# PCB-MIDI-OUT.net
KiCad netlist of a schematic drawn in EAGLE
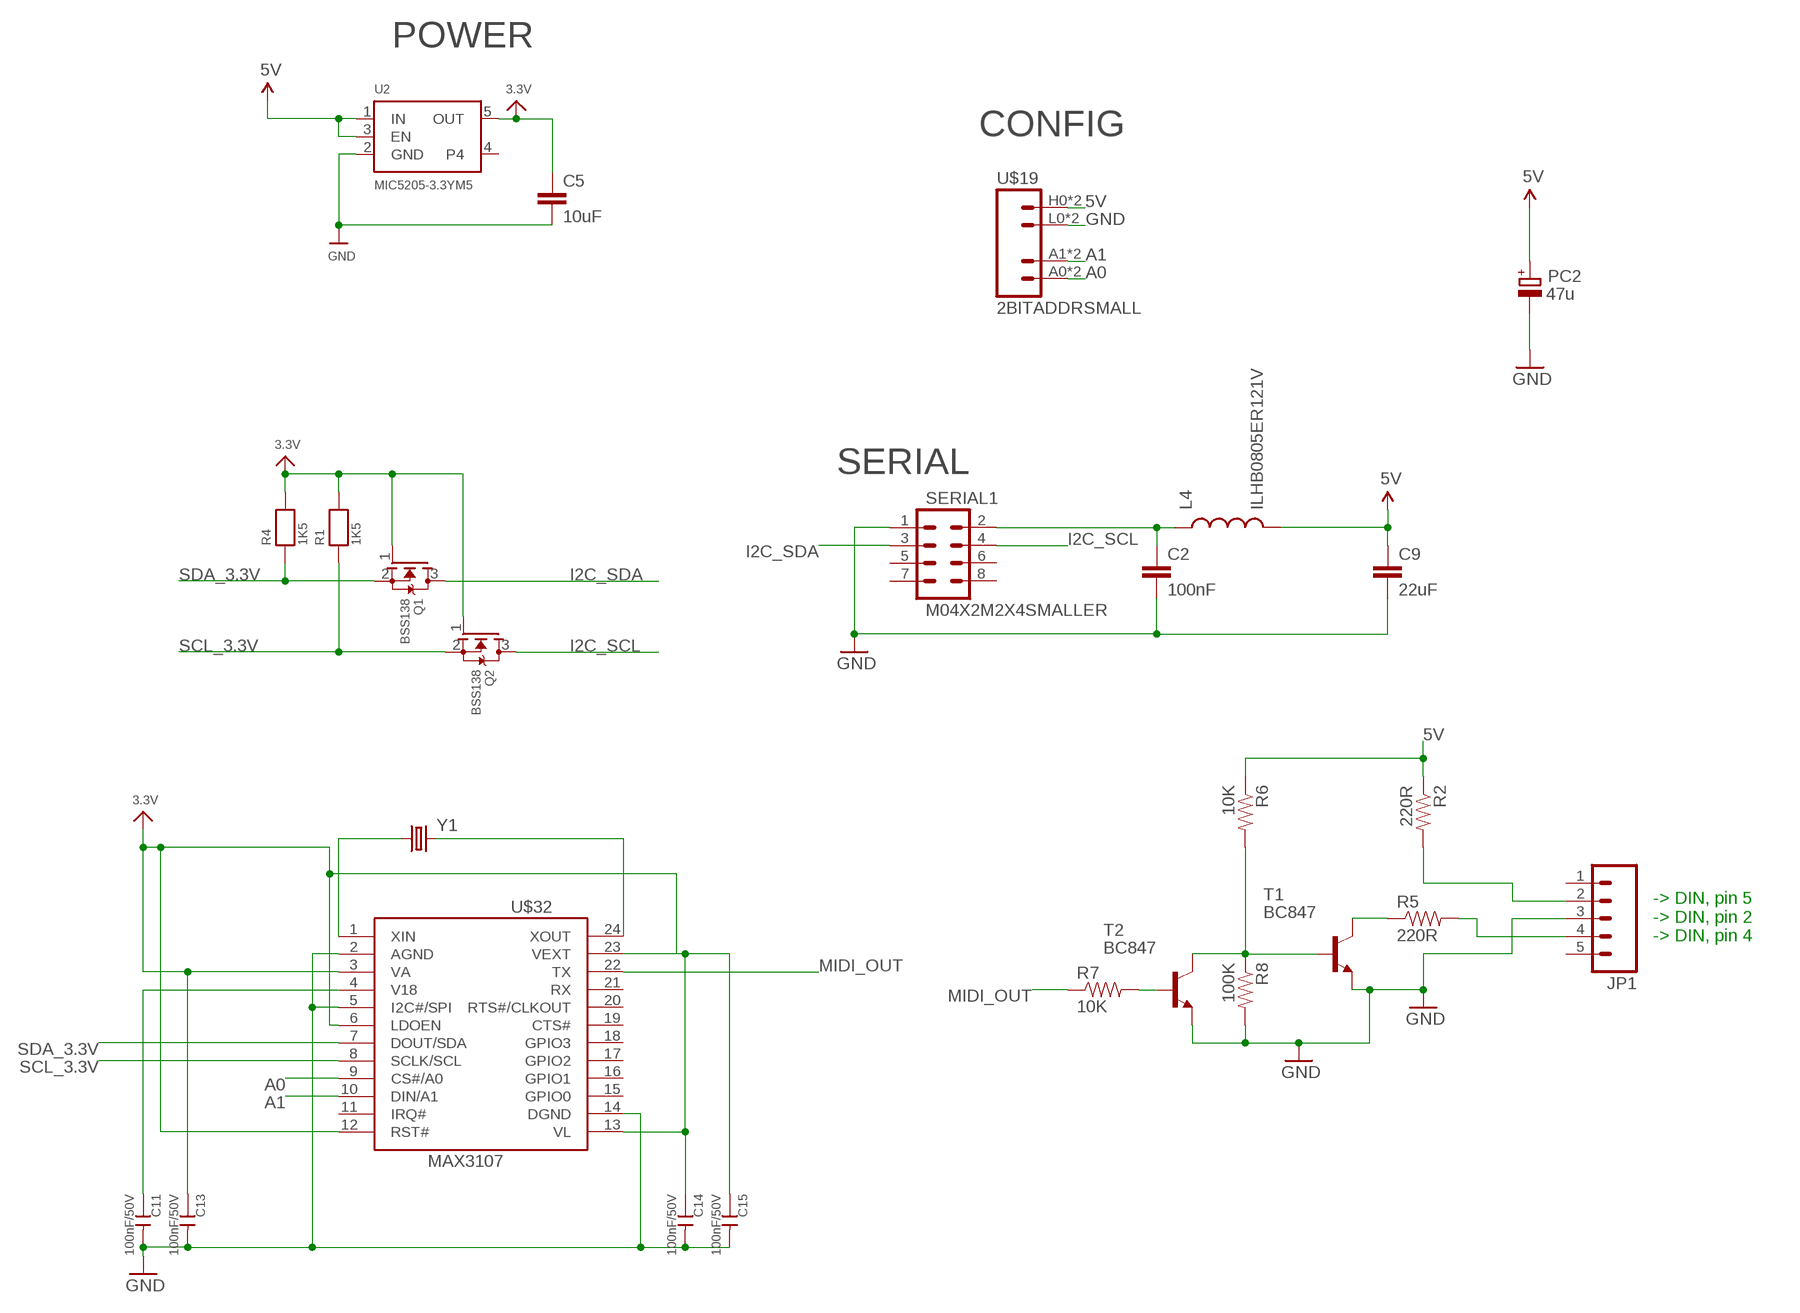
[diagram p0: schematic, sheet 1]

(export (version "E")
  (design (tool "Eeschema 10.0.6"))
  (components
    (comp (ref "C2")
      (value "100nF")
      (footprint "eagle-import:0603-CAP")
      (libsource (lib "eagle-import") (part "CAP0603-CAP"))
    )
    (comp (ref "C5")
      (value "10uF")
      (footprint "eagle-import:0805")
      (libsource (lib "eagle-import") (part "CAP0805"))
    )
    (comp (ref "C9")
      (value "22uF")
      (footprint "eagle-import:0805")
      (libsource (lib "eagle-import") (part "CAP0805"))
    )
    (comp (ref "C11")
      (value "100nF/50V")
      (footprint "eagle-import:C0603")
      (libsource (lib "eagle-import") (part "CAP-0603"))
    )
    (comp (ref "C13")
      (value "100nF/50V")
      (footprint "eagle-import:C0603")
      (libsource (lib "eagle-import") (part "CAP-0603"))
    )
    (comp (ref "C14")
      (value "100nF/50V")
      (footprint "eagle-import:C0603")
      (libsource (lib "eagle-import") (part "CAP-0603"))
    )
    (comp (ref "C15")
      (value "100nF/50V")
      (footprint "eagle-import:C0603")
      (libsource (lib "eagle-import") (part "CAP-0603"))
    )
    (comp (ref "JP1")
      (value "M05LOCK")
      (footprint "eagle-import:1X05_LOCK")
      (libsource (lib "eagle-import") (part "M05LOCK"))
    )
    (comp (ref "L4")
      (value "ILHB0805ER121V")
      (footprint "eagle-import:0805")
      (libsource (lib "eagle-import") (part "INDUCTOR0805"))
    )
    (comp (ref "PC2")
      (value "47u")
      (footprint "eagle-import:PANASONIC_D")
      (libsource (lib "eagle-import") (part "CPOL-EUD"))
    )
    (comp (ref "Q1")
      (value "BSS138")
      (footprint "eagle-import:SOT23-R")
      (libsource (lib "eagle-import") (part "MOSFET-NREFLOW"))
    )
    (comp (ref "Q2")
      (value "BSS138")
      (footprint "eagle-import:SOT23-R")
      (libsource (lib "eagle-import") (part "MOSFET-NREFLOW"))
    )
    (comp (ref "R1")
      (value "1K5")
      (footprint "eagle-import:0603")
      (libsource (lib "eagle-import") (part "RESISTOR0603"))
    )
    (comp (ref "R2")
      (value "220R")
      (footprint "eagle-import:0603-RES")
      (libsource (lib "eagle-import") (part "RESISTOR0603-RES"))
    )
    (comp (ref "R4")
      (value "1K5")
      (footprint "eagle-import:0603")
      (libsource (lib "eagle-import") (part "RESISTOR0603"))
    )
    (comp (ref "R5")
      (value "220R")
      (footprint "eagle-import:0603-RES")
      (libsource (lib "eagle-import") (part "RESISTOR0603-RES"))
    )
    (comp (ref "R6")
      (value "10K")
      (footprint "eagle-import:0603-RES")
      (libsource (lib "eagle-import") (part "RESISTOR0603-RES"))
    )
    (comp (ref "R7")
      (value "10K")
      (footprint "eagle-import:0603-RES")
      (libsource (lib "eagle-import") (part "RESISTOR0603-RES"))
    )
    (comp (ref "R8")
      (value "100K")
      (footprint "eagle-import:0603-RES")
      (libsource (lib "eagle-import") (part "RESISTOR0603-RES"))
    )
    (comp (ref "SERIAL1")
      (value "M04X2M2X4SMALLER")
      (footprint "eagle-import:M2X4SMALLER")
      (libsource (lib "eagle-import") (part "M04X2M2X4SMALLER"))
    )
    (comp (ref "T1")
      (value "BC847")
      (footprint "eagle-import:SOT23")
      (libsource (lib "eagle-import") (part "BC847"))
    )
    (comp (ref "T2")
      (value "BC847")
      (footprint "eagle-import:SOT23")
      (libsource (lib "eagle-import") (part "BC847"))
    )
    (comp (ref "U$19")
      (value "2BITADDRSMALL")
      (footprint "eagle-import:2BITADDR_SMALL")
      (libsource (lib "eagle-import") (part "2BITADDRSMALL"))
    )
    (comp (ref "U$32")
      (value "MAX3107")
      (footprint "eagle-import:SSOP24")
      (libsource (lib "eagle-import") (part "MAX3107"))
    )
    (comp (ref "U2")
      (value "MIC5205-3.3YM5")
      (footprint "eagle-import:SOT23-5")
      (libsource (lib "eagle-import") (part "VREG_SOT23-5"))
    )
    (comp (ref "Y1")
      (value "CRYSTALHC49US")
      (footprint "eagle-import:HC49US")
      (libsource (lib "eagle-import") (part "CRYSTALHC49US"))
    )
  )
  (nets
    (net (code "1") (name "3.3V") (class "Default")
      (node (ref "C13") (pin "1") (pinfunction "1_1") (pintype "passive"))
      (node (ref "C14") (pin "1") (pinfunction "1_1") (pintype "passive"))
      (node (ref "C15") (pin "1") (pinfunction "1_1") (pintype "passive"))
      (node (ref "C5") (pin "1") (pinfunction "1_1") (pintype "passive"))
      (node (ref "Q1") (pin "1") (pinfunction "G_1") (pintype "bidirectional"))
      (node (ref "Q2") (pin "1") (pinfunction "G_1") (pintype "bidirectional"))
      (node (ref "R1") (pin "2") (pinfunction "2_2") (pintype "passive"))
      (node (ref "R4") (pin "2") (pinfunction "2_2") (pintype "passive"))
      (node (ref "U$32") (pin "12") (pinfunction "RST#_12") (pintype "input"))
      (node (ref "U$32") (pin "13") (pinfunction "VL_13") (pintype "power_in"))
      (node (ref "U$32") (pin "23") (pinfunction "VEXT_23") (pintype "power_in"))
      (node (ref "U$32") (pin "3") (pinfunction "VA_3") (pintype "power_in"))
      (node (ref "U$32") (pin "6") (pinfunction "LDOEN_6") (pintype "input"))
      (node (ref "U2") (pin "5") (pinfunction "OUT_5") (pintype "bidirectional"))
    )
    (net (code "2") (name "5V") (class "Default")
      (node (ref "C9") (pin "1") (pinfunction "1_1") (pintype "passive"))
      (node (ref "L4") (pin "2") (pinfunction "2_2") (pintype "passive"))
      (node (ref "PC2") (pin "+") (pinfunction "+_+") (pintype "passive"))
      (node (ref "R2") (pin "1") (pinfunction "1_1") (pintype "passive"))
      (node (ref "R6") (pin "1") (pinfunction "1_1") (pintype "passive"))
      (node (ref "U$19") (pin "H0") (pinfunction "VCC_H0") (pintype "passive"))
      (node (ref "U$19") (pin "H1") (pinfunction "VCC_H1") (pintype "passive"))
      (node (ref "U2") (pin "1") (pinfunction "IN_1") (pintype "bidirectional"))
      (node (ref "U2") (pin "3") (pinfunction "EN_3") (pintype "bidirectional"))
    )
    (net (code "3") (name "A0") (class "Default")
      (node (ref "U$19") (pin "A0") (pinfunction "A1_A0") (pintype "passive"))
      (node (ref "U$19") (pin "AS0") (pinfunction "A1_AS0") (pintype "passive"))
      (node (ref "U$32") (pin "9") (pinfunction "CS#/A0_9") (pintype "input"))
    )
    (net (code "4") (name "A1") (class "Default")
      (node (ref "U$19") (pin "A1") (pinfunction "A2_A1") (pintype "passive"))
      (node (ref "U$19") (pin "AS1") (pinfunction "A2_AS1") (pintype "passive"))
      (node (ref "U$32") (pin "10") (pinfunction "DIN/A1_10") (pintype "input"))
    )
    (net (code "5") (name "GND") (class "Default")
      (node (ref "C11") (pin "2") (pinfunction "2_2") (pintype "passive"))
      (node (ref "C13") (pin "2") (pinfunction "2_2") (pintype "passive"))
      (node (ref "C14") (pin "2") (pinfunction "2_2") (pintype "passive"))
      (node (ref "C15") (pin "2") (pinfunction "2_2") (pintype "passive"))
      (node (ref "C2") (pin "2") (pinfunction "2_2") (pintype "passive"))
      (node (ref "C5") (pin "2") (pinfunction "2_2") (pintype "passive"))
      (node (ref "C9") (pin "2") (pinfunction "2_2") (pintype "passive"))
      (node (ref "JP1") (pin "3") (pinfunction "3_3") (pintype "passive"))
      (node (ref "PC2") (pin "-") (pinfunction "-_-") (pintype "passive"))
      (node (ref "R8") (pin "2") (pinfunction "2_2") (pintype "passive"))
      (node (ref "SERIAL1") (pin "1") (pinfunction "1_1") (pintype "passive"))
      (node (ref "T1") (pin "2") (pinfunction "E_2") (pintype "passive"))
      (node (ref "T2") (pin "2") (pinfunction "E_2") (pintype "passive"))
      (node (ref "U$19") (pin "L0") (pinfunction "GND_L0") (pintype "passive"))
      (node (ref "U$19") (pin "L1") (pinfunction "GND_L1") (pintype "passive"))
      (node (ref "U$32") (pin "14") (pinfunction "DGND_14") (pintype "power_in"))
      (node (ref "U$32") (pin "2") (pinfunction "AGND_2") (pintype "power_in"))
      (node (ref "U$32") (pin "5") (pinfunction "I2C#/SPI_5") (pintype "input"))
      (node (ref "U2") (pin "2") (pinfunction "GND_2") (pintype "bidirectional"))
    )
    (net (code "6") (name "I2C_SCL") (class "Default")
      (node (ref "Q2") (pin "3") (pinfunction "D_3") (pintype "bidirectional"))
      (node (ref "SERIAL1") (pin "4") (pinfunction "4_4") (pintype "passive"))
    )
    (net (code "7") (name "I2C_SDA") (class "Default")
      (node (ref "Q1") (pin "3") (pinfunction "D_3") (pintype "bidirectional"))
      (node (ref "SERIAL1") (pin "3") (pinfunction "3_3") (pintype "passive"))
    )
    (net (code "8") (name "MIDI_OUT") (class "Default")
      (node (ref "R7") (pin "1") (pinfunction "1_1") (pintype "passive"))
      (node (ref "U$32") (pin "22") (pinfunction "TX_22") (pintype "output"))
    )
    (net (code "9") (name "Net-(C2-Pad1)") (class "Default")
      (node (ref "C2") (pin "1") (pinfunction "1_1") (pintype "passive"))
      (node (ref "L4") (pin "1") (pinfunction "1_1") (pintype "passive"))
      (node (ref "SERIAL1") (pin "2") (pinfunction "2_2") (pintype "passive"))
    )
    (net (code "10") (name "Net-(JP1-Pad2)") (class "Default")
      (node (ref "JP1") (pin "2") (pinfunction "2_2") (pintype "passive"))
      (node (ref "R2") (pin "2") (pinfunction "2_2") (pintype "passive"))
    )
    (net (code "11") (name "Net-(JP1-Pad4)") (class "Default")
      (node (ref "JP1") (pin "4") (pinfunction "4_4") (pintype "passive"))
      (node (ref "R5") (pin "2") (pinfunction "2_2") (pintype "passive"))
    )
    (net (code "12") (name "Net-(T1-B)") (class "Default")
      (node (ref "R6") (pin "2") (pinfunction "2_2") (pintype "passive"))
      (node (ref "R8") (pin "1") (pinfunction "1_1") (pintype "passive"))
      (node (ref "T1") (pin "1") (pinfunction "B_1") (pintype "passive"))
      (node (ref "T2") (pin "3") (pinfunction "C_3") (pintype "passive"))
    )
    (net (code "13") (name "Net-(T1-C)") (class "Default")
      (node (ref "R5") (pin "1") (pinfunction "1_1") (pintype "passive"))
      (node (ref "T1") (pin "3") (pinfunction "C_3") (pintype "passive"))
    )
    (net (code "14") (name "Net-(T2-B)") (class "Default")
      (node (ref "R7") (pin "2") (pinfunction "2_2") (pintype "passive"))
      (node (ref "T2") (pin "1") (pinfunction "B_1") (pintype "passive"))
    )
    (net (code "15") (name "Net-(U$32-V18)") (class "Default")
      (node (ref "C11") (pin "1") (pinfunction "1_1") (pintype "passive"))
      (node (ref "U$32") (pin "4") (pinfunction "V18_4") (pintype "output"))
    )
    (net (code "16") (name "Net-(U$32-XIN)") (class "Default")
      (node (ref "U$32") (pin "1") (pinfunction "XIN_1") (pintype "bidirectional"))
      (node (ref "Y1") (pin "1") (pinfunction "1_1") (pintype "passive"))
    )
    (net (code "17") (name "Net-(U$32-XOUT)") (class "Default")
      (node (ref "U$32") (pin "24") (pinfunction "XOUT_24") (pintype "bidirectional"))
      (node (ref "Y1") (pin "2") (pinfunction "2_2") (pintype "passive"))
    )
    (net (code "18") (name "SCL_3.3V") (class "Default")
      (node (ref "Q2") (pin "2") (pinfunction "S_2") (pintype "bidirectional"))
      (node (ref "R1") (pin "1") (pinfunction "1_1") (pintype "passive"))
      (node (ref "U$32") (pin "8") (pinfunction "SCLK/SCL_8") (pintype "input"))
    )
    (net (code "19") (name "SDA_3.3V") (class "Default")
      (node (ref "Q1") (pin "2") (pinfunction "S_2") (pintype "bidirectional"))
      (node (ref "R4") (pin "1") (pinfunction "1_1") (pintype "passive"))
      (node (ref "U$32") (pin "7") (pinfunction "DOUT/SDA_7") (pintype "bidirectional"))
    )
    (net (code "20") (name "unconnected-(JP1-Pad1)") (class "Default")
      (node (ref "JP1") (pin "1") (pinfunction "1_1") (pintype "passive"))
    )
    (net (code "21") (name "unconnected-(JP1-Pad5)") (class "Default")
      (node (ref "JP1") (pin "5") (pinfunction "5_5") (pintype "passive"))
    )
    (net (code "22") (name "unconnected-(SERIAL1-Pad5)") (class "Default")
      (node (ref "SERIAL1") (pin "5") (pinfunction "5_5") (pintype "passive"))
    )
    (net (code "23") (name "unconnected-(SERIAL1-Pad6)") (class "Default")
      (node (ref "SERIAL1") (pin "6") (pinfunction "6_6") (pintype "passive"))
    )
    (net (code "24") (name "unconnected-(SERIAL1-Pad7)") (class "Default")
      (node (ref "SERIAL1") (pin "7") (pinfunction "7_7") (pintype "passive"))
    )
    (net (code "25") (name "unconnected-(SERIAL1-Pad8)") (class "Default")
      (node (ref "SERIAL1") (pin "8") (pinfunction "8_8") (pintype "passive"))
    )
    (net (code "26") (name "unconnected-(U$32-CTS#-Pad19)") (class "Default")
      (node (ref "U$32") (pin "19") (pinfunction "CTS#_19") (pintype "bidirectional"))
    )
    (net (code "27") (name "unconnected-(U$32-GPIO0-Pad15)") (class "Default")
      (node (ref "U$32") (pin "15") (pinfunction "GPIO0_15") (pintype "bidirectional"))
    )
    (net (code "28") (name "unconnected-(U$32-GPIO1-Pad16)") (class "Default")
      (node (ref "U$32") (pin "16") (pinfunction "GPIO1_16") (pintype "bidirectional"))
    )
    (net (code "29") (name "unconnected-(U$32-GPIO2-Pad17)") (class "Default")
      (node (ref "U$32") (pin "17") (pinfunction "GPIO2_17") (pintype "bidirectional"))
    )
    (net (code "30") (name "unconnected-(U$32-GPIO3-Pad18)") (class "Default")
      (node (ref "U$32") (pin "18") (pinfunction "GPIO3_18") (pintype "bidirectional"))
    )
    (net (code "31") (name "unconnected-(U$32-IRQ#-Pad11)") (class "Default")
      (node (ref "U$32") (pin "11") (pinfunction "IRQ#_11") (pintype "output"))
    )
    (net (code "32") (name "unconnected-(U$32-RTS#{slash}CLKOUT-Pad20)") (class "Default")
      (node (ref "U$32") (pin "20") (pinfunction "RTS#/CLKOUT_20") (pintype "bidirectional"))
    )
    (net (code "33") (name "unconnected-(U$32-RX-Pad21)") (class "Default")
      (node (ref "U$32") (pin "21") (pinfunction "RX_21") (pintype "input"))
    )
    (net (code "34") (name "unconnected-(U2-P4-Pad4)") (class "Default")
      (node (ref "U2") (pin "4") (pinfunction "P4_4") (pintype "bidirectional"))
    )
  )
)
